# SOIC-16_Breakout_Board.net
KiCad netlist of a schematic drawn in EAGLE
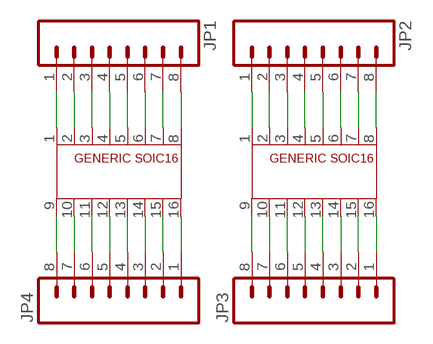
[diagram p0: schematic, sheet 1]

(export (version "E")
  (design (tool "Eeschema 10.0.6"))
  (components
    (comp (ref "JP1")
      (value "M08")
      (footprint "eagle-import:1X08")
      (libsource (lib "eagle-import") (part "M08"))
    )
    (comp (ref "JP2")
      (value "M08")
      (footprint "eagle-import:1X08")
      (libsource (lib "eagle-import") (part "M08"))
    )
    (comp (ref "JP3")
      (value "M08")
      (footprint "eagle-import:1X08")
      (libsource (lib "eagle-import") (part "M08"))
    )
    (comp (ref "JP4")
      (value "M08")
      (footprint "eagle-import:1X08")
      (libsource (lib "eagle-import") (part "M08"))
    )
    (comp (ref "U$1")
      (value "SOIC16")
      (footprint "eagle-import:SOIC-16")
      (libsource (lib "eagle-import") (part "SOIC16"))
    )
    (comp (ref "U$2")
      (value "SOIC16")
      (footprint "eagle-import:SOIC-16")
      (libsource (lib "eagle-import") (part "SOIC16"))
    )
  )
  (nets
    (net (code "1") (name "Net-(U$1-P$1)") (class "Default")
      (node (ref "JP1") (pin "1") (pinfunction "1_1") (pintype "passive"))
      (node (ref "U$1") (pin "1") (pinfunction "P$1_1") (pintype "bidirectional"))
    )
    (net (code "2") (name "Net-(U$1-P$2)") (class "Default")
      (node (ref "JP1") (pin "2") (pinfunction "2_2") (pintype "passive"))
      (node (ref "U$1") (pin "2") (pinfunction "P$2_2") (pintype "bidirectional"))
    )
    (net (code "3") (name "Net-(U$1-P$3)") (class "Default")
      (node (ref "JP1") (pin "3") (pinfunction "3_3") (pintype "passive"))
      (node (ref "U$1") (pin "3") (pinfunction "P$3_3") (pintype "bidirectional"))
    )
    (net (code "4") (name "Net-(U$1-P$4)") (class "Default")
      (node (ref "JP1") (pin "4") (pinfunction "4_4") (pintype "passive"))
      (node (ref "U$1") (pin "4") (pinfunction "P$4_4") (pintype "bidirectional"))
    )
    (net (code "5") (name "Net-(U$1-P$5)") (class "Default")
      (node (ref "JP1") (pin "5") (pinfunction "5_5") (pintype "passive"))
      (node (ref "U$1") (pin "5") (pinfunction "P$5_5") (pintype "bidirectional"))
    )
    (net (code "6") (name "Net-(U$1-P$6)") (class "Default")
      (node (ref "JP1") (pin "6") (pinfunction "6_6") (pintype "passive"))
      (node (ref "U$1") (pin "6") (pinfunction "P$6_6") (pintype "bidirectional"))
    )
    (net (code "7") (name "Net-(U$1-P$7)") (class "Default")
      (node (ref "JP1") (pin "7") (pinfunction "7_7") (pintype "passive"))
      (node (ref "U$1") (pin "7") (pinfunction "P$7_7") (pintype "bidirectional"))
    )
    (net (code "8") (name "Net-(U$1-P$8)") (class "Default")
      (node (ref "JP1") (pin "8") (pinfunction "8_8") (pintype "passive"))
      (node (ref "U$1") (pin "8") (pinfunction "P$8_8") (pintype "bidirectional"))
    )
    (net (code "9") (name "Net-(U$1-P$9)") (class "Default")
      (node (ref "JP4") (pin "8") (pinfunction "8_8") (pintype "passive"))
      (node (ref "U$1") (pin "9") (pinfunction "P$9_9") (pintype "bidirectional"))
    )
    (net (code "10") (name "Net-(U$1-P$10)") (class "Default")
      (node (ref "JP4") (pin "7") (pinfunction "7_7") (pintype "passive"))
      (node (ref "U$1") (pin "10") (pinfunction "P$10_10") (pintype "bidirectional"))
    )
    (net (code "11") (name "Net-(U$1-P$11)") (class "Default")
      (node (ref "JP4") (pin "6") (pinfunction "6_6") (pintype "passive"))
      (node (ref "U$1") (pin "11") (pinfunction "P$11_11") (pintype "bidirectional"))
    )
    (net (code "12") (name "Net-(U$1-P$12)") (class "Default")
      (node (ref "JP4") (pin "5") (pinfunction "5_5") (pintype "passive"))
      (node (ref "U$1") (pin "12") (pinfunction "P$12_12") (pintype "bidirectional"))
    )
    (net (code "13") (name "Net-(U$1-P$13)") (class "Default")
      (node (ref "JP4") (pin "4") (pinfunction "4_4") (pintype "passive"))
      (node (ref "U$1") (pin "13") (pinfunction "P$13_13") (pintype "bidirectional"))
    )
    (net (code "14") (name "Net-(U$1-P$14)") (class "Default")
      (node (ref "JP4") (pin "3") (pinfunction "3_3") (pintype "passive"))
      (node (ref "U$1") (pin "14") (pinfunction "P$14_14") (pintype "bidirectional"))
    )
    (net (code "15") (name "Net-(U$1-P$15)") (class "Default")
      (node (ref "JP4") (pin "2") (pinfunction "2_2") (pintype "passive"))
      (node (ref "U$1") (pin "15") (pinfunction "P$15_15") (pintype "bidirectional"))
    )
    (net (code "16") (name "Net-(U$1-P$16)") (class "Default")
      (node (ref "JP4") (pin "1") (pinfunction "1_1") (pintype "passive"))
      (node (ref "U$1") (pin "16") (pinfunction "P$16_16") (pintype "bidirectional"))
    )
    (net (code "17") (name "Net-(U$2-P$1)") (class "Default")
      (node (ref "JP2") (pin "1") (pinfunction "1_1") (pintype "passive"))
      (node (ref "U$2") (pin "1") (pinfunction "P$1_1") (pintype "bidirectional"))
    )
    (net (code "18") (name "Net-(U$2-P$2)") (class "Default")
      (node (ref "JP2") (pin "2") (pinfunction "2_2") (pintype "passive"))
      (node (ref "U$2") (pin "2") (pinfunction "P$2_2") (pintype "bidirectional"))
    )
    (net (code "19") (name "Net-(U$2-P$3)") (class "Default")
      (node (ref "JP2") (pin "3") (pinfunction "3_3") (pintype "passive"))
      (node (ref "U$2") (pin "3") (pinfunction "P$3_3") (pintype "bidirectional"))
    )
    (net (code "20") (name "Net-(U$2-P$4)") (class "Default")
      (node (ref "JP2") (pin "4") (pinfunction "4_4") (pintype "passive"))
      (node (ref "U$2") (pin "4") (pinfunction "P$4_4") (pintype "bidirectional"))
    )
    (net (code "21") (name "Net-(U$2-P$5)") (class "Default")
      (node (ref "JP2") (pin "5") (pinfunction "5_5") (pintype "passive"))
      (node (ref "U$2") (pin "5") (pinfunction "P$5_5") (pintype "bidirectional"))
    )
    (net (code "22") (name "Net-(U$2-P$6)") (class "Default")
      (node (ref "JP2") (pin "6") (pinfunction "6_6") (pintype "passive"))
      (node (ref "U$2") (pin "6") (pinfunction "P$6_6") (pintype "bidirectional"))
    )
    (net (code "23") (name "Net-(U$2-P$7)") (class "Default")
      (node (ref "JP2") (pin "7") (pinfunction "7_7") (pintype "passive"))
      (node (ref "U$2") (pin "7") (pinfunction "P$7_7") (pintype "bidirectional"))
    )
    (net (code "24") (name "Net-(U$2-P$8)") (class "Default")
      (node (ref "JP2") (pin "8") (pinfunction "8_8") (pintype "passive"))
      (node (ref "U$2") (pin "8") (pinfunction "P$8_8") (pintype "bidirectional"))
    )
    (net (code "25") (name "Net-(U$2-P$9)") (class "Default")
      (node (ref "JP3") (pin "8") (pinfunction "8_8") (pintype "passive"))
      (node (ref "U$2") (pin "9") (pinfunction "P$9_9") (pintype "bidirectional"))
    )
    (net (code "26") (name "Net-(U$2-P$10)") (class "Default")
      (node (ref "JP3") (pin "7") (pinfunction "7_7") (pintype "passive"))
      (node (ref "U$2") (pin "10") (pinfunction "P$10_10") (pintype "bidirectional"))
    )
    (net (code "27") (name "Net-(U$2-P$11)") (class "Default")
      (node (ref "JP3") (pin "6") (pinfunction "6_6") (pintype "passive"))
      (node (ref "U$2") (pin "11") (pinfunction "P$11_11") (pintype "bidirectional"))
    )
    (net (code "28") (name "Net-(U$2-P$12)") (class "Default")
      (node (ref "JP3") (pin "5") (pinfunction "5_5") (pintype "passive"))
      (node (ref "U$2") (pin "12") (pinfunction "P$12_12") (pintype "bidirectional"))
    )
    (net (code "29") (name "Net-(U$2-P$13)") (class "Default")
      (node (ref "JP3") (pin "4") (pinfunction "4_4") (pintype "passive"))
      (node (ref "U$2") (pin "13") (pinfunction "P$13_13") (pintype "bidirectional"))
    )
    (net (code "30") (name "Net-(U$2-P$14)") (class "Default")
      (node (ref "JP3") (pin "3") (pinfunction "3_3") (pintype "passive"))
      (node (ref "U$2") (pin "14") (pinfunction "P$14_14") (pintype "bidirectional"))
    )
    (net (code "31") (name "Net-(U$2-P$15)") (class "Default")
      (node (ref "JP3") (pin "2") (pinfunction "2_2") (pintype "passive"))
      (node (ref "U$2") (pin "15") (pinfunction "P$15_15") (pintype "bidirectional"))
    )
    (net (code "32") (name "Net-(U$2-P$16)") (class "Default")
      (node (ref "JP3") (pin "1") (pinfunction "1_1") (pintype "passive"))
      (node (ref "U$2") (pin "16") (pinfunction "P$16_16") (pintype "bidirectional"))
    )
  )
)
